# sensorNodeRev2.net
KiCad netlist of a schematic drawn in EAGLE
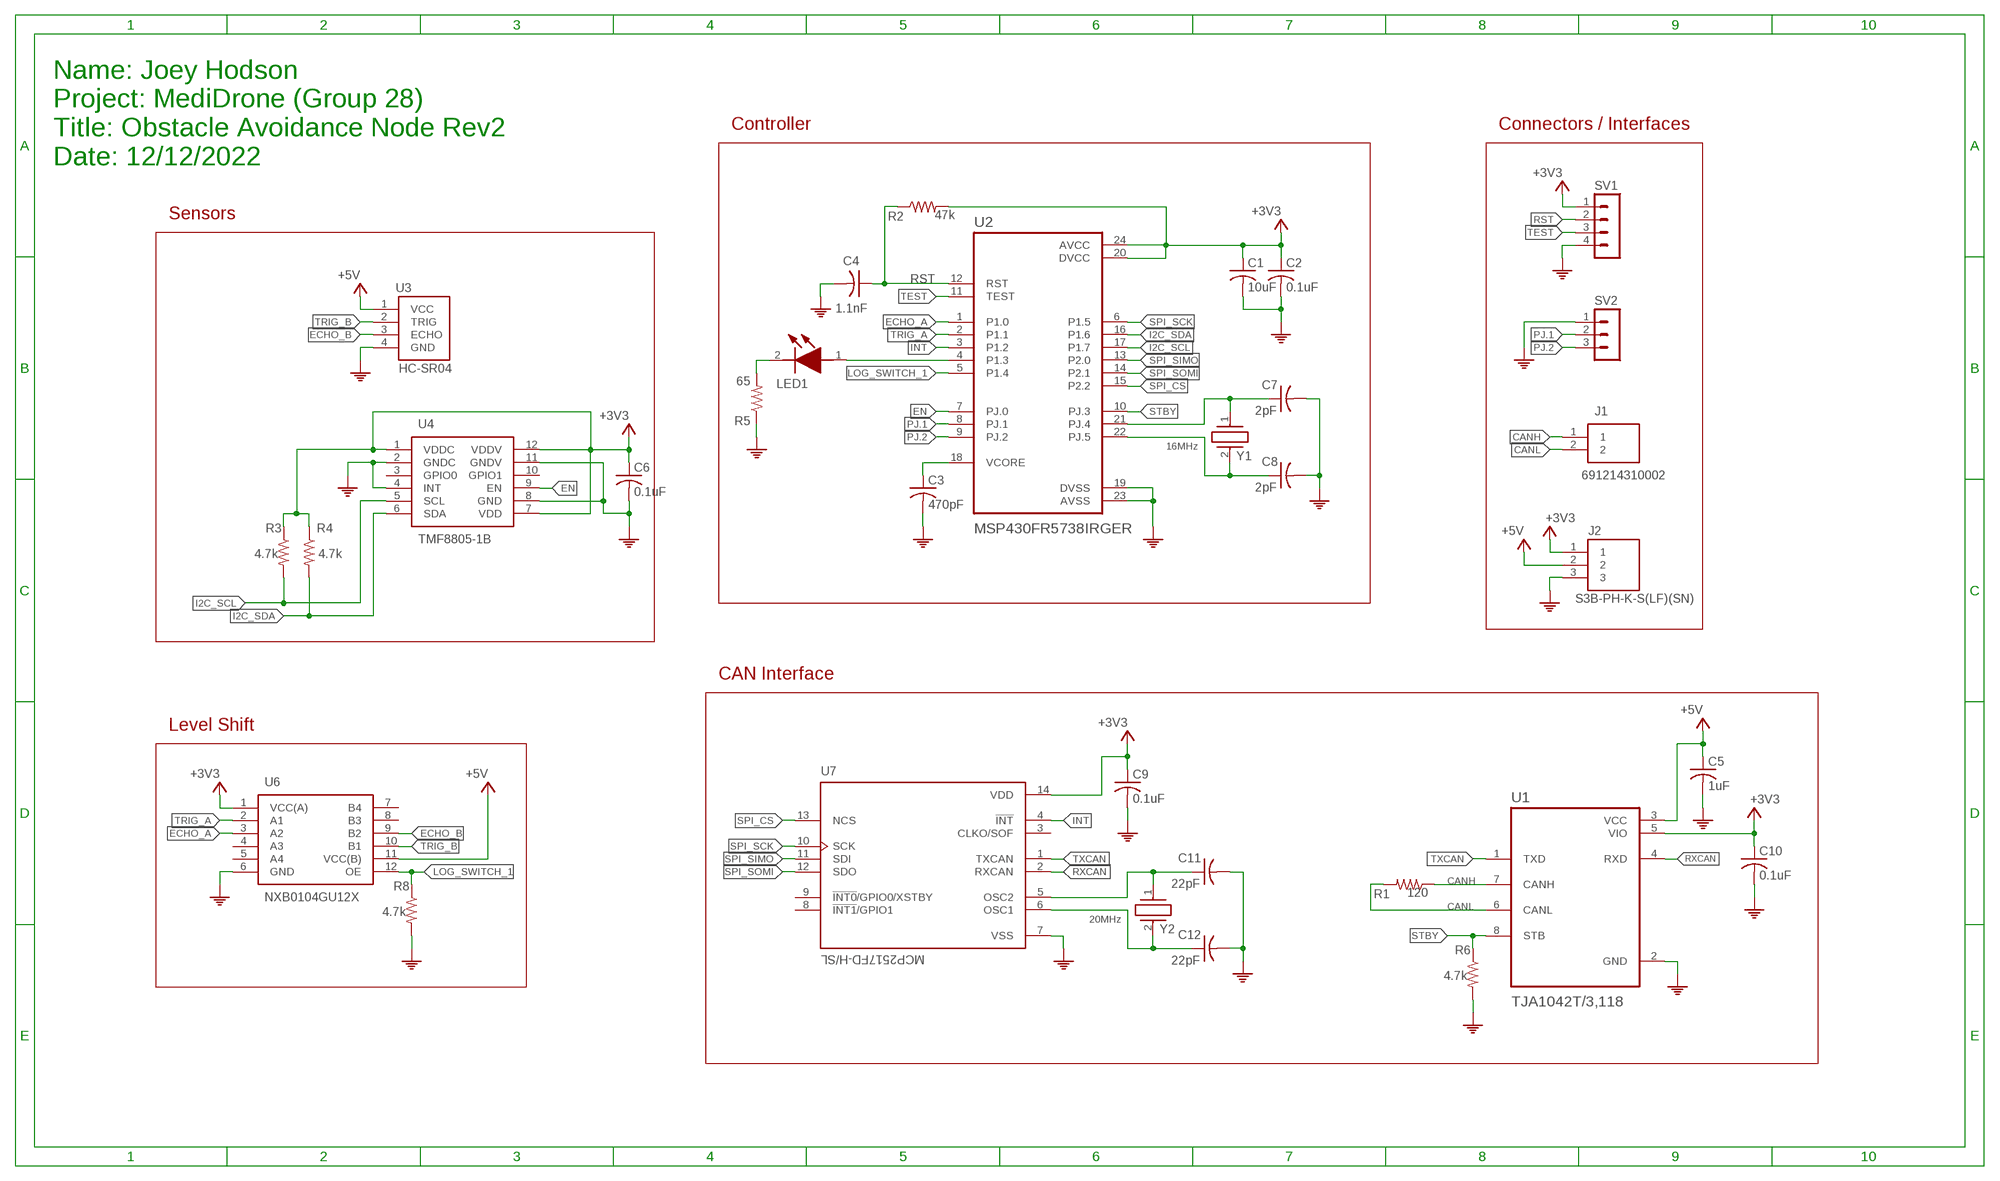
[diagram p0: schematic, sheet 1]

(export (version "E")
  (design (tool "Eeschema 10.0.6"))
  (components
    (comp (ref "C1")
      (value "10uF")
      (footprint "eagle-import:C0805")
      (libsource (lib "eagle-import") (part "C-USC0805"))
    )
    (comp (ref "C2")
      (value "0.1uF")
      (footprint "eagle-import:C0603")
      (libsource (lib "eagle-import") (part "C-USC0603"))
    )
    (comp (ref "C3")
      (value "470pF")
      (footprint "eagle-import:C0603")
      (libsource (lib "eagle-import") (part "C-USC0603"))
    )
    (comp (ref "C4")
      (value "1.1nF")
      (footprint "eagle-import:C0603")
      (libsource (lib "eagle-import") (part "C-USC0603"))
    )
    (comp (ref "C5")
      (value "1uF")
      (footprint "eagle-import:C0603")
      (libsource (lib "eagle-import") (part "C-USC0603"))
    )
    (comp (ref "C6")
      (value "0.1uF")
      (footprint "eagle-import:C0603")
      (libsource (lib "eagle-import") (part "C-USC0603"))
    )
    (comp (ref "C7")
      (value "2pF")
      (footprint "eagle-import:C0603")
      (libsource (lib "eagle-import") (part "C-USC0603"))
    )
    (comp (ref "C8")
      (value "2pF")
      (footprint "eagle-import:C0603")
      (libsource (lib "eagle-import") (part "C-USC0603"))
    )
    (comp (ref "C9")
      (value "0.1uF")
      (footprint "eagle-import:C0603")
      (libsource (lib "eagle-import") (part "C-USC0603"))
    )
    (comp (ref "C10")
      (value "0.1uF")
      (footprint "eagle-import:C0603")
      (libsource (lib "eagle-import") (part "C-USC0603"))
    )
    (comp (ref "C11")
      (value "22pF")
      (footprint "eagle-import:C0603")
      (libsource (lib "eagle-import") (part "C-USC0603"))
    )
    (comp (ref "C12")
      (value "22pF")
      (footprint "eagle-import:C0603")
      (libsource (lib "eagle-import") (part "C-USC0603"))
    )
    (comp (ref "J1")
      (value "691214310002")
      (footprint "eagle-import:SHDR2W90P0X381_1X2_802X740X850")
      (fields (field (name "MOUSER_PART_NUMBER") "710-691214310002"))
      (libsource (lib "eagle-import") (part "691214310002"))
    )
    (comp (ref "J2")
      (value "S3B-PH-K-S(LF)(SN)")
      (footprint "eagle-import:JST_S3B-PH-K-S(LF)(SN)")
      (fields (field (name "MF") "JST Sales"))
      (libsource (lib "eagle-import") (part "S3B-PH-K-S(LF)(SN)"))
    )
    (comp (ref "LED1")
      (value "SML-LX0603IW-TR")
      (footprint "eagle-import:SMLLX0603IWTR")
      (fields (field (name "MOUSER_PART_NUMBER") "696-SML-LX0603IW"))
      (libsource (lib "eagle-import") (part "SML-LX0603IW-TR"))
    )
    (comp (ref "R1")
      (value "120")
      (footprint "eagle-import:R0603")
      (libsource (lib "eagle-import") (part "R-US_R0603"))
    )
    (comp (ref "R2")
      (value "47k")
      (footprint "eagle-import:R0603")
      (libsource (lib "eagle-import") (part "R-US_R0603"))
    )
    (comp (ref "R3")
      (value "4.7k")
      (footprint "eagle-import:R0603")
      (libsource (lib "eagle-import") (part "R-US_R0603"))
    )
    (comp (ref "R4")
      (value "4.7k")
      (footprint "eagle-import:R0603")
      (libsource (lib "eagle-import") (part "R-US_R0603"))
    )
    (comp (ref "R5")
      (value "65")
      (footprint "eagle-import:R0603")
      (libsource (lib "eagle-import") (part "R-US_R0603"))
    )
    (comp (ref "R6")
      (value "4.7k")
      (footprint "eagle-import:R0603")
      (libsource (lib "eagle-import") (part "R-US_R0603"))
    )
    (comp (ref "R8")
      (value "4.7k")
      (footprint "eagle-import:R0603")
      (libsource (lib "eagle-import") (part "R-US_R0603"))
    )
    (comp (ref "SV1")
      (value "MA04-1")
      (footprint "eagle-import:MA04-1")
      (libsource (lib "eagle-import") (part "MA04-1"))
    )
    (comp (ref "SV2")
      (value "MA03-1")
      (footprint "eagle-import:MA03-1")
      (libsource (lib "eagle-import") (part "MA03-1"))
    )
    (comp (ref "U1")
      (value "TJA1042T/3,118")
      (footprint "eagle-import:SOIC127P600X175-8N")
      (fields (field (name "MF") "NXP USA"))
      (libsource (lib "eagle-import") (part "TJA1042T/3,118"))
    )
    (comp (ref "U2")
      (value "MSP430FR5738IRGER")
      (footprint "eagle-import:QFN50P400X400X100-25N")
      (fields (field (name "MF") "Texas Instruments"))
      (libsource (lib "eagle-import") (part "MSP430FR5738IRGER"))
    )
    (comp (ref "U3")
      (value "HC-SR04")
      (footprint "eagle-import:HC-SR04_VARIANT")
      (fields (field (name "MF") "OSEPP Electronics"))
      (libsource (lib "eagle-import") (part "HC-SR04"))
    )
    (comp (ref "U4")
      (value "TMF8805-1B")
      (footprint "eagle-import:TMF88051B")
      (fields (field (name "MOUSER_PART_NUMBER") "985-TMF8805-1B"))
      (libsource (lib "eagle-import") (part "TMF8805-1B"))
    )
    (comp (ref "U6")
      (value "NXB0104GU12X")
      (footprint "eagle-import:NXB0104GU12X")
      (fields (field (name "MOUSER_PART_NUMBER") "771-NXB0104GU12X"))
      (libsource (lib "eagle-import") (part "NXB0104GU12X"))
    )
    (comp (ref "U7")
      (value "MCP2517FD-H/SL")
      (footprint "eagle-import:SOIC127P600X175-14N")
      (fields (field (name "MF") "Microchip"))
      (libsource (lib "eagle-import") (part "MCP2517FD-H/SL"))
    )
    (comp (ref "Y1")
      (value "HC-49_U-S16000000ABJB")
      (footprint "eagle-import:HC49")
      (fields
        (field (name "MANUFACTURER_PART_NUMBER") "HC-49/U-S16000000ABJB")
        (field (name "MOUSER_PART_NUMBER") "695-HC49US16.0ABJB")
      )
      (libsource (lib "eagle-import") (part "HC-49_U-S16000000ABJB"))
    )
    (comp (ref "Y2")
      (value "HC-49_U-S16000000ABJB")
      (footprint "eagle-import:HC49")
      (fields
        (field (name "MANUFACTURER_PART_NUMBER") "HC-49/U-S16000000ABJB")
        (field (name "MOUSER_PART_NUMBER") "695-HC49US16.0ABJB")
      )
      (libsource (lib "eagle-import") (part "HC-49_U-S16000000ABJB"))
    )
  )
  (nets
    (net (code "1") (name "+3V3") (class "Default")
      (node (ref "C1") (pin "1") (pinfunction "1_1") (pintype "passive"))
      (node (ref "C10") (pin "1") (pinfunction "1_1") (pintype "passive"))
      (node (ref "C2") (pin "1") (pinfunction "1_1") (pintype "passive"))
      (node (ref "C6") (pin "1") (pinfunction "1_1") (pintype "passive"))
      (node (ref "C9") (pin "1") (pinfunction "1_1") (pintype "passive"))
      (node (ref "J2") (pin "1") (pinfunction "1_1") (pintype "passive"))
      (node (ref "R2") (pin "2") (pinfunction "2_2") (pintype "passive"))
      (node (ref "R3") (pin "1") (pinfunction "1_1") (pintype "passive"))
      (node (ref "R4") (pin "1") (pinfunction "1_1") (pintype "passive"))
      (node (ref "SV1") (pin "1") (pinfunction "1_1") (pintype "passive"))
      (node (ref "U1") (pin "5") (pinfunction "VIO_5") (pintype "power_in"))
      (node (ref "U2") (pin "20") (pinfunction "DVCC_20") (pintype "power_in"))
      (node (ref "U2") (pin "24") (pinfunction "AVCC_24") (pintype "power_in"))
      (node (ref "U4") (pin "1") (pinfunction "VDDC_1") (pintype "bidirectional"))
      (node (ref "U4") (pin "12") (pinfunction "VDDV_12") (pintype "bidirectional"))
      (node (ref "U4") (pin "7") (pinfunction "VDD_7") (pintype "bidirectional"))
      (node (ref "U6") (pin "1") (pinfunction "VCC(A)_1") (pintype "bidirectional"))
      (node (ref "U7") (pin "14") (pinfunction "VDD_14") (pintype "power_in"))
    )
    (net (code "2") (name "+5V") (class "Default")
      (node (ref "C5") (pin "1") (pinfunction "1_1") (pintype "passive"))
      (node (ref "J2") (pin "2") (pinfunction "2_2") (pintype "passive"))
      (node (ref "U1") (pin "3") (pinfunction "VCC_3") (pintype "power_in"))
      (node (ref "U3") (pin "1") (pinfunction "VCC_1") (pintype "power_in"))
      (node (ref "U6") (pin "11") (pinfunction "VCC(B)_11") (pintype "bidirectional"))
    )
    (net (code "3") (name "CANH") (class "Default")
      (node (ref "J1") (pin "1") (pinfunction "1_1") (pintype "bidirectional"))
      (node (ref "R1") (pin "1") (pinfunction "1_1") (pintype "passive"))
      (node (ref "U1") (pin "7") (pinfunction "CANH_7") (pintype "bidirectional"))
    )
    (net (code "4") (name "CANL") (class "Default")
      (node (ref "J1") (pin "2") (pinfunction "2_2") (pintype "bidirectional"))
      (node (ref "R1") (pin "2") (pinfunction "2_2") (pintype "passive"))
      (node (ref "U1") (pin "6") (pinfunction "CANL_6") (pintype "bidirectional"))
    )
    (net (code "5") (name "ECHO_A") (class "Default")
      (node (ref "U2") (pin "1") (pinfunction "P1.0_1") (pintype "bidirectional"))
      (node (ref "U6") (pin "3") (pinfunction "A2_3") (pintype "bidirectional"))
    )
    (net (code "6") (name "ECHO_B") (class "Default")
      (node (ref "U3") (pin "3") (pinfunction "ECHO_3") (pintype "bidirectional"))
      (node (ref "U6") (pin "9") (pinfunction "B2_9") (pintype "bidirectional"))
    )
    (net (code "7") (name "EN") (class "Default")
      (node (ref "U2") (pin "7") (pinfunction "PJ.0_7") (pintype "bidirectional"))
      (node (ref "U4") (pin "9") (pinfunction "EN_9") (pintype "bidirectional"))
    )
    (net (code "8") (name "I2C_SCL") (class "Default")
      (node (ref "R3") (pin "2") (pinfunction "2_2") (pintype "passive"))
      (node (ref "U2") (pin "17") (pinfunction "P1.7_17") (pintype "bidirectional"))
      (node (ref "U4") (pin "5") (pinfunction "SCL_5") (pintype "bidirectional"))
    )
    (net (code "9") (name "I2C_SDA") (class "Default")
      (node (ref "R4") (pin "2") (pinfunction "2_2") (pintype "passive"))
      (node (ref "U2") (pin "16") (pinfunction "P1.6_16") (pintype "bidirectional"))
      (node (ref "U4") (pin "6") (pinfunction "SDA_6") (pintype "bidirectional"))
    )
    (net (code "10") (name "INT") (class "Default")
      (node (ref "U2") (pin "3") (pinfunction "P1.2_3") (pintype "bidirectional"))
      (node (ref "U7") (pin "4") (pinfunction "~{INT}_4") (pintype "output"))
    )
    (net (code "11") (name "LOG_SWITCH_1") (class "Default")
      (node (ref "R8") (pin "1") (pinfunction "1_1") (pintype "passive"))
      (node (ref "U2") (pin "5") (pinfunction "P1.4_5") (pintype "bidirectional"))
      (node (ref "U6") (pin "12") (pinfunction "OE_12") (pintype "bidirectional"))
    )
    (net (code "12") (name "Net-(LED1-A)") (class "Default")
      (node (ref "LED1") (pin "1") (pinfunction "A_1") (pintype "bidirectional"))
      (node (ref "U2") (pin "4") (pinfunction "P1.3_4") (pintype "bidirectional"))
    )
    (net (code "13") (name "Net-(LED1-K)") (class "Default")
      (node (ref "LED1") (pin "2") (pinfunction "K_2") (pintype "bidirectional"))
      (node (ref "R5") (pin "2") (pinfunction "2_2") (pintype "passive"))
    )
    (net (code "14") (name "Net-(U2-PJ.4)") (class "Default")
      (node (ref "C7") (pin "1") (pinfunction "1_1") (pintype "passive"))
      (node (ref "U2") (pin "21") (pinfunction "PJ.4_21") (pintype "bidirectional"))
      (node (ref "Y1") (pin "1") (pinfunction "1_1") (pintype "bidirectional"))
    )
    (net (code "15") (name "Net-(U2-PJ.5)") (class "Default")
      (node (ref "C8") (pin "1") (pinfunction "1_1") (pintype "passive"))
      (node (ref "U2") (pin "22") (pinfunction "PJ.5_22") (pintype "bidirectional"))
      (node (ref "Y1") (pin "2") (pinfunction "2_2") (pintype "bidirectional"))
    )
    (net (code "16") (name "Net-(U2-VCORE)") (class "Default")
      (node (ref "C3") (pin "1") (pinfunction "1_1") (pintype "passive"))
      (node (ref "U2") (pin "18") (pinfunction "VCORE_18") (pintype "bidirectional"))
    )
    (net (code "17") (name "Net-(U7-OSC1)") (class "Default")
      (node (ref "C12") (pin "1") (pinfunction "1_1") (pintype "passive"))
      (node (ref "U7") (pin "6") (pinfunction "OSC1_6") (pintype "input"))
      (node (ref "Y2") (pin "2") (pinfunction "2_2") (pintype "bidirectional"))
    )
    (net (code "18") (name "Net-(U7-OSC2)") (class "Default")
      (node (ref "C11") (pin "1") (pinfunction "1_1") (pintype "passive"))
      (node (ref "U7") (pin "5") (pinfunction "OSC2_5") (pintype "output"))
      (node (ref "Y2") (pin "1") (pinfunction "1_1") (pintype "bidirectional"))
    )
    (net (code "19") (name "PE") (class "Default")
      (node (ref "C1") (pin "2") (pinfunction "2_2") (pintype "passive"))
      (node (ref "C10") (pin "2") (pinfunction "2_2") (pintype "passive"))
      (node (ref "C11") (pin "2") (pinfunction "2_2") (pintype "passive"))
      (node (ref "C12") (pin "2") (pinfunction "2_2") (pintype "passive"))
      (node (ref "C2") (pin "2") (pinfunction "2_2") (pintype "passive"))
      (node (ref "C3") (pin "2") (pinfunction "2_2") (pintype "passive"))
      (node (ref "C4") (pin "2") (pinfunction "2_2") (pintype "passive"))
      (node (ref "C5") (pin "2") (pinfunction "2_2") (pintype "passive"))
      (node (ref "C6") (pin "2") (pinfunction "2_2") (pintype "passive"))
      (node (ref "C7") (pin "2") (pinfunction "2_2") (pintype "passive"))
      (node (ref "C8") (pin "2") (pinfunction "2_2") (pintype "passive"))
      (node (ref "C9") (pin "2") (pinfunction "2_2") (pintype "passive"))
      (node (ref "J2") (pin "3") (pinfunction "3_3") (pintype "passive"))
      (node (ref "R5") (pin "1") (pinfunction "1_1") (pintype "passive"))
      (node (ref "R6") (pin "2") (pinfunction "2_2") (pintype "passive"))
      (node (ref "R8") (pin "2") (pinfunction "2_2") (pintype "passive"))
      (node (ref "SV1") (pin "4") (pinfunction "4_4") (pintype "passive"))
      (node (ref "SV2") (pin "1") (pinfunction "1_1") (pintype "passive"))
      (node (ref "U1") (pin "2") (pinfunction "GND_2") (pintype "power_in"))
      (node (ref "U2") (pin "19") (pinfunction "DVSS_19") (pintype "power_in"))
      (node (ref "U2") (pin "23") (pinfunction "AVSS_23") (pintype "power_in"))
      (node (ref "U3") (pin "4") (pinfunction "GND_4") (pintype "power_in"))
      (node (ref "U4") (pin "11") (pinfunction "GNDV_11") (pintype "bidirectional"))
      (node (ref "U4") (pin "2") (pinfunction "GNDC_2") (pintype "bidirectional"))
      (node (ref "U4") (pin "4") (pinfunction "INT_4") (pintype "bidirectional"))
      (node (ref "U4") (pin "8") (pinfunction "GND_8") (pintype "bidirectional"))
      (node (ref "U6") (pin "6") (pinfunction "GND_6") (pintype "bidirectional"))
      (node (ref "U7") (pin "7") (pinfunction "VSS_7") (pintype "power_in"))
    )
    (net (code "20") (name "PJ.1") (class "Default")
      (node (ref "SV2") (pin "2") (pinfunction "2_2") (pintype "passive"))
      (node (ref "U2") (pin "8") (pinfunction "PJ.1_8") (pintype "bidirectional"))
    )
    (net (code "21") (name "PJ.2") (class "Default")
      (node (ref "SV2") (pin "3") (pinfunction "3_3") (pintype "passive"))
      (node (ref "U2") (pin "9") (pinfunction "PJ.2_9") (pintype "bidirectional"))
    )
    (net (code "22") (name "RST") (class "Default")
      (node (ref "C4") (pin "1") (pinfunction "1_1") (pintype "passive"))
      (node (ref "R2") (pin "1") (pinfunction "1_1") (pintype "passive"))
      (node (ref "SV1") (pin "2") (pinfunction "2_2") (pintype "passive"))
      (node (ref "U2") (pin "12") (pinfunction "RST_12") (pintype "input"))
    )
    (net (code "23") (name "RXCAN") (class "Default")
      (node (ref "U1") (pin "4") (pinfunction "RXD_4") (pintype "output"))
      (node (ref "U7") (pin "2") (pinfunction "RXCAN_2") (pintype "input"))
    )
    (net (code "24") (name "SPI_CS") (class "Default")
      (node (ref "U2") (pin "15") (pinfunction "P2.2_15") (pintype "bidirectional"))
      (node (ref "U7") (pin "13") (pinfunction "NCS_13") (pintype "input"))
    )
    (net (code "25") (name "SPI_SCK") (class "Default")
      (node (ref "U2") (pin "6") (pinfunction "P1.5_6") (pintype "bidirectional"))
      (node (ref "U7") (pin "10") (pinfunction "SCK_10") (pintype "input"))
    )
    (net (code "26") (name "SPI_SIMO") (class "Default")
      (node (ref "U2") (pin "13") (pinfunction "P2.0_13") (pintype "bidirectional"))
      (node (ref "U7") (pin "11") (pinfunction "SDI_11") (pintype "input"))
    )
    (net (code "27") (name "SPI_SOMI") (class "Default")
      (node (ref "U2") (pin "14") (pinfunction "P2.1_14") (pintype "bidirectional"))
      (node (ref "U7") (pin "12") (pinfunction "SDO_12") (pintype "output"))
    )
    (net (code "28") (name "STBY") (class "Default")
      (node (ref "R6") (pin "1") (pinfunction "1_1") (pintype "passive"))
      (node (ref "U1") (pin "8") (pinfunction "STB_8") (pintype "bidirectional"))
      (node (ref "U2") (pin "10") (pinfunction "PJ.3_10") (pintype "bidirectional"))
    )
    (net (code "29") (name "TEST") (class "Default")
      (node (ref "SV1") (pin "3") (pinfunction "3_3") (pintype "passive"))
      (node (ref "U2") (pin "11") (pinfunction "TEST_11") (pintype "input"))
    )
    (net (code "30") (name "TRIG_A") (class "Default")
      (node (ref "U2") (pin "2") (pinfunction "P1.1_2") (pintype "bidirectional"))
      (node (ref "U6") (pin "2") (pinfunction "A1_2") (pintype "bidirectional"))
    )
    (net (code "31") (name "TRIG_B") (class "Default")
      (node (ref "U3") (pin "2") (pinfunction "TRIG_2") (pintype "bidirectional"))
      (node (ref "U6") (pin "10") (pinfunction "B1_10") (pintype "bidirectional"))
    )
    (net (code "32") (name "TXCAN") (class "Default")
      (node (ref "U1") (pin "1") (pinfunction "TXD_1") (pintype "input"))
      (node (ref "U7") (pin "1") (pinfunction "TXCAN_1") (pintype "output"))
    )
    (net (code "33") (name "unconnected-(U4-GPIO0-Pad3)") (class "Default")
      (node (ref "U4") (pin "3") (pinfunction "GPIO0_3") (pintype "bidirectional"))
    )
    (net (code "34") (name "unconnected-(U4-GPIO1-Pad10)") (class "Default")
      (node (ref "U4") (pin "10") (pinfunction "GPIO1_10") (pintype "bidirectional"))
    )
    (net (code "35") (name "unconnected-(U6-A3-Pad4)") (class "Default")
      (node (ref "U6") (pin "4") (pinfunction "A3_4") (pintype "bidirectional"))
    )
    (net (code "36") (name "unconnected-(U6-A4-Pad5)") (class "Default")
      (node (ref "U6") (pin "5") (pinfunction "A4_5") (pintype "bidirectional"))
    )
    (net (code "37") (name "unconnected-(U6-B3-Pad8)") (class "Default")
      (node (ref "U6") (pin "8") (pinfunction "B3_8") (pintype "bidirectional"))
    )
    (net (code "38") (name "unconnected-(U6-B4-Pad7)") (class "Default")
      (node (ref "U6") (pin "7") (pinfunction "B4_7") (pintype "bidirectional"))
    )
    (net (code "39") (name "unconnected-(U7-CLKO{slash}SOF-Pad3)") (class "Default")
      (node (ref "U7") (pin "3") (pinfunction "CLKO/SOF_3") (pintype "output"))
    )
    (net (code "40") (name "unconnected-(U7-~{INT0}{slash}GPIO0{slash}XSTBY-Pad9)") (class "Default")
      (node (ref "U7") (pin "9") (pinfunction "~{INT0}/GPIO0/XSTBY_9") (pintype "bidirectional"))
    )
    (net (code "41") (name "unconnected-(U7-~{INT1}{slash}GPIO1-Pad8)") (class "Default")
      (node (ref "U7") (pin "8") (pinfunction "~{INT1}/GPIO1_8") (pintype "bidirectional"))
    )
  )
)
